# currentV_cond.net
KiCad netlist of a schematic drawn in Altium Designer
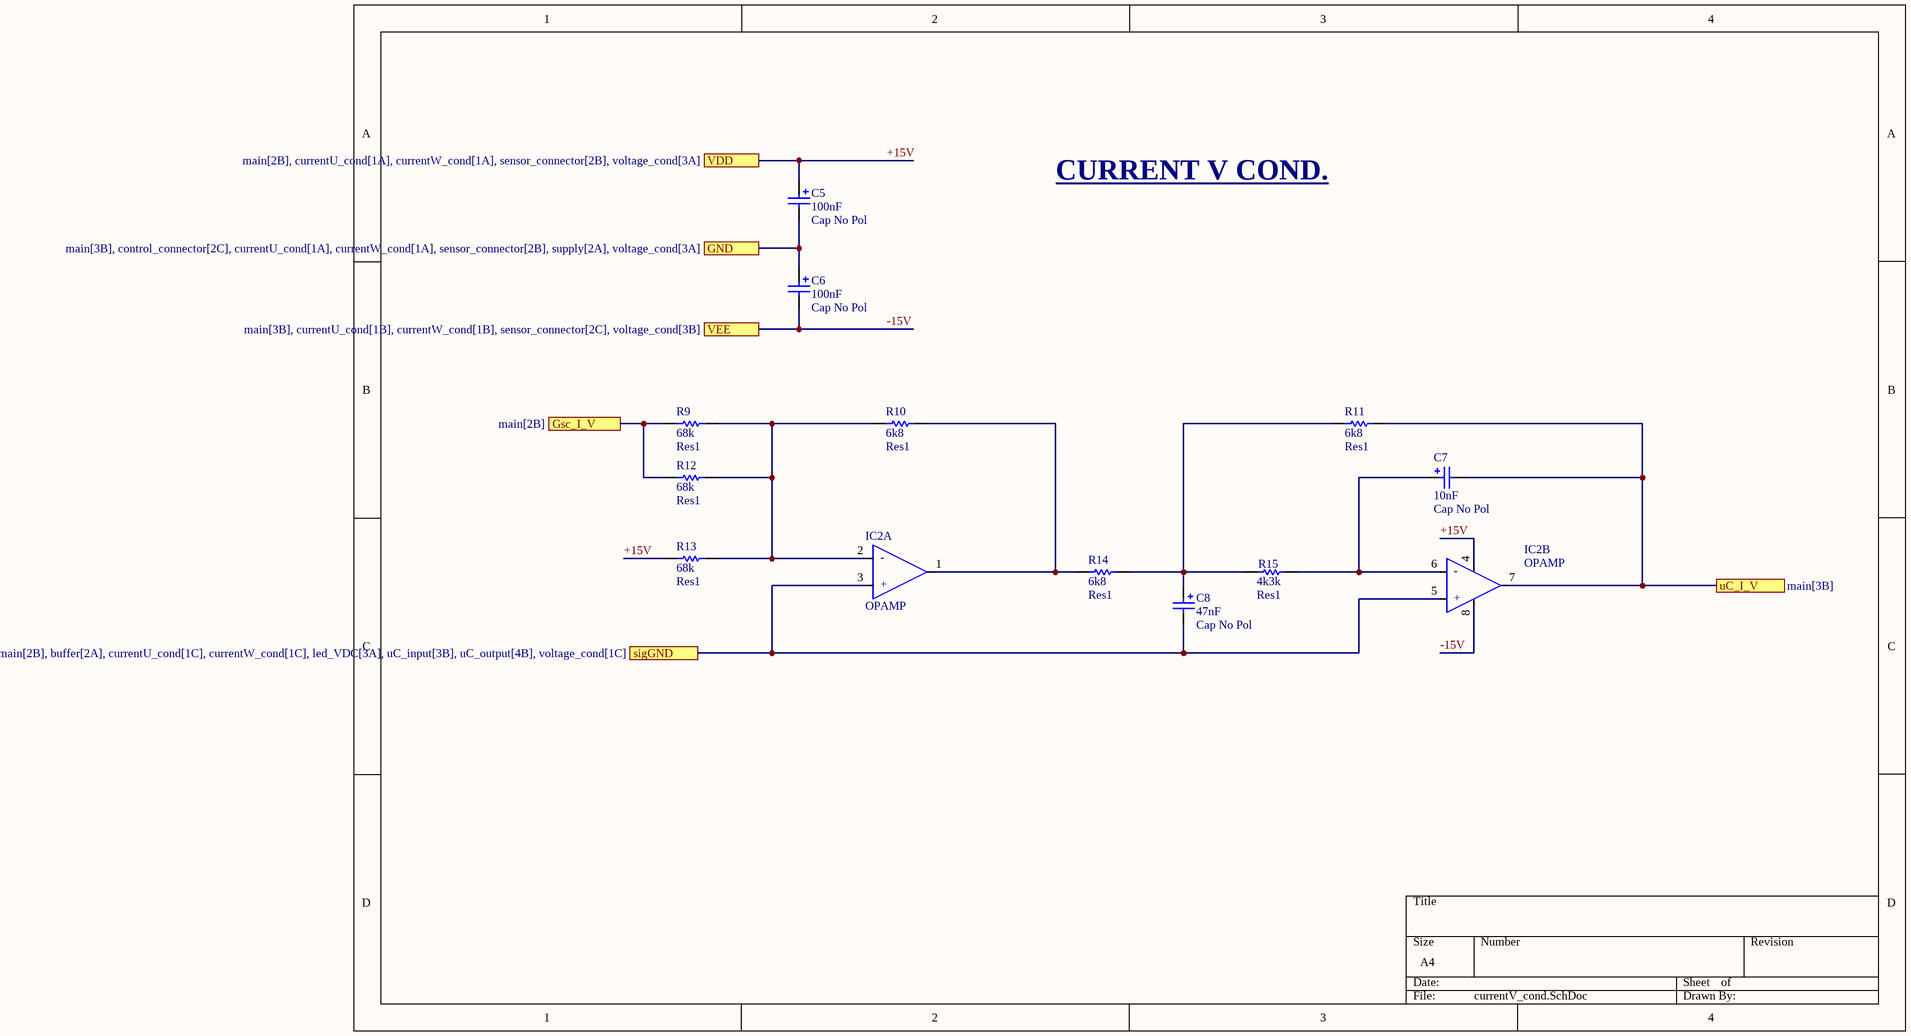
[diagram p0: currentV_cond.SchDoc]

(export (version "E")
  (design (tool "Eeschema 10.0.6"))
  (components
    (comp (ref "C5")
      (value "Cap No Pol")
      (footprint "RAD-0.1_mod")
      (description "Polarized Capacitor (Radial)")
      (fields (field (name "ALTIUM_VALUE") "100nF") (field (name "PUBLISHER") "Altium Limited"))
      (libsource (lib "LABSTEPS_Project") (part "Cap No Pol"))
    )
    (comp (ref "C6")
      (value "Cap No Pol")
      (footprint "RAD-0.1_mod")
      (description "Polarized Capacitor (Radial)")
      (fields (field (name "ALTIUM_VALUE") "100nF") (field (name "PUBLISHER") "Altium Limited"))
      (libsource (lib "LABSTEPS_Project") (part "Cap No Pol"))
    )
    (comp (ref "C7")
      (value "Cap No Pol")
      (footprint "RAD-0.1_mod")
      (description "Polarized Capacitor (Radial)")
      (fields (field (name "ALTIUM_VALUE") "10nF") (field (name "PUBLISHER") "Altium Limited"))
      (libsource (lib "LABSTEPS_Project") (part "Cap No Pol"))
    )
    (comp (ref "C8")
      (value "Cap No Pol")
      (footprint "RAD-0.1_mod")
      (description "Polarized Capacitor (Radial)")
      (fields (field (name "ALTIUM_VALUE") "47nF") (field (name "PUBLISHER") "Altium Limited"))
      (libsource (lib "LABSTEPS_Project") (part "Cap No Pol"))
    )
    (comp (ref "IC2")
      (value "OPAMP")
      (footprint "DIP-8_mod")
      (description "ADTL082")
      (libsource (lib "LABSTEPS_Project") (part "ADTL082"))
    )
    (comp (ref "R9")
      (value "Res1")
      (footprint "AXIAL-0.3_mod")
      (description "Resistor")
      (fields (field (name "ALTIUM_VALUE") "68k") (field (name "PUBLISHER") "Altium Limited"))
      (libsource (lib "LABSTEPS_Project") (part "Res1"))
    )
    (comp (ref "R10")
      (value "Res1")
      (footprint "AXIAL-0.3_mod")
      (description "Resistor")
      (fields (field (name "ALTIUM_VALUE") "6k8") (field (name "PUBLISHER") "Altium Limited"))
      (libsource (lib "LABSTEPS_Project") (part "Res1"))
    )
    (comp (ref "R11")
      (value "Res1")
      (footprint "AXIAL-0.3_mod")
      (description "Resistor")
      (fields (field (name "ALTIUM_VALUE") "6k8") (field (name "PUBLISHER") "Altium Limited"))
      (libsource (lib "LABSTEPS_Project") (part "Res1"))
    )
    (comp (ref "R12")
      (value "Res1")
      (footprint "AXIAL-0.3_mod")
      (description "Resistor")
      (fields (field (name "ALTIUM_VALUE") "68k") (field (name "PUBLISHER") "Altium Limited"))
      (libsource (lib "LABSTEPS_Project") (part "Res1"))
    )
    (comp (ref "R13")
      (value "Res1")
      (footprint "AXIAL-0.3_mod")
      (description "Resistor")
      (fields (field (name "ALTIUM_VALUE") "68k") (field (name "PUBLISHER") "Altium Limited"))
      (libsource (lib "LABSTEPS_Project") (part "Res1"))
    )
    (comp (ref "R14")
      (value "Res1")
      (footprint "AXIAL-0.3_mod")
      (description "Resistor")
      (fields (field (name "ALTIUM_VALUE") "6k8") (field (name "PUBLISHER") "Altium Limited"))
      (libsource (lib "LABSTEPS_Project") (part "Res1"))
    )
    (comp (ref "R15")
      (value "Res1")
      (footprint "AXIAL-0.3_mod")
      (description "Resistor")
      (fields (field (name "ALTIUM_VALUE") "4k3k") (field (name "PUBLISHER") "Altium Limited"))
      (libsource (lib "LABSTEPS_Project") (part "Res1"))
    )
  )
  (nets
    (net (code "1") (name "/+15V") (class "Default")
      (node (ref "C5") (pin "1") (pinfunction "1_1") (pintype "passive"))
      (node (ref "IC2") (pin "4") (pinfunction "-V_4") (pintype "passive"))
      (node (ref "R13") (pin "1") (pinfunction "1_1") (pintype "passive"))
    )
    (net (code "2") (name "/-15V") (class "Default")
      (node (ref "C6") (pin "2") (pinfunction "2_2") (pintype "passive"))
      (node (ref "IC2") (pin "8") (pinfunction "V+_8") (pintype "passive"))
    )
    (net (code "3") (name "/GND") (class "Default")
      (node (ref "C5") (pin "2") (pinfunction "2_2") (pintype "passive"))
      (node (ref "C6") (pin "1") (pinfunction "1_1") (pintype "passive"))
    )
    (net (code "4") (name "/Gsc_I_V") (class "Default")
      (node (ref "R12") (pin "1") (pinfunction "1_1") (pintype "passive"))
      (node (ref "R9") (pin "1") (pinfunction "1_1") (pintype "passive"))
    )
    (net (code "5") (name "/sigGND") (class "Default")
      (node (ref "C8") (pin "2") (pinfunction "2_2") (pintype "passive"))
      (node (ref "IC2") (pin "3") (pinfunction "IN_A_+_3") (pintype "passive"))
      (node (ref "IC2") (pin "5") (pinfunction "IN_B_+_5") (pintype "passive"))
    )
    (net (code "6") (name "/uC_I_V") (class "Default")
      (node (ref "C7") (pin "2") (pinfunction "2_2") (pintype "passive"))
      (node (ref "IC2") (pin "7") (pinfunction "OUT_B_7") (pintype "passive"))
      (node (ref "R11") (pin "2") (pinfunction "2_2") (pintype "passive"))
    )
    (net (code "7") (name "Net-(C8-Pad1)") (class "Default")
      (node (ref "C8") (pin "1") (pinfunction "1_1") (pintype "passive"))
      (node (ref "R11") (pin "1") (pinfunction "1_1") (pintype "passive"))
      (node (ref "R14") (pin "2") (pinfunction "2_2") (pintype "passive"))
      (node (ref "R15") (pin "1") (pinfunction "1_1") (pintype "passive"))
    )
    (net (code "8") (name "Net-(IC2A-IN_A_-)") (class "Default")
      (node (ref "IC2") (pin "2") (pinfunction "IN_A_-_2") (pintype "passive"))
      (node (ref "R10") (pin "1") (pinfunction "1_1") (pintype "passive"))
      (node (ref "R12") (pin "2") (pinfunction "2_2") (pintype "passive"))
      (node (ref "R13") (pin "2") (pinfunction "2_2") (pintype "passive"))
      (node (ref "R9") (pin "2") (pinfunction "2_2") (pintype "passive"))
    )
    (net (code "9") (name "Net-(IC2A-OUT_A)") (class "Default")
      (node (ref "IC2") (pin "1") (pinfunction "OUT_A_1") (pintype "passive"))
      (node (ref "R10") (pin "2") (pinfunction "2_2") (pintype "passive"))
      (node (ref "R14") (pin "1") (pinfunction "1_1") (pintype "passive"))
    )
    (net (code "10") (name "Net-(IC2B-IN_B_-)") (class "Default")
      (node (ref "C7") (pin "1") (pinfunction "1_1") (pintype "passive"))
      (node (ref "IC2") (pin "6") (pinfunction "IN_B_-_6") (pintype "passive"))
      (node (ref "R15") (pin "2") (pinfunction "2_2") (pintype "passive"))
    )
  )
)
